# ADXL375_BOARD.net
KiCad netlist of a schematic drawn in EAGLE
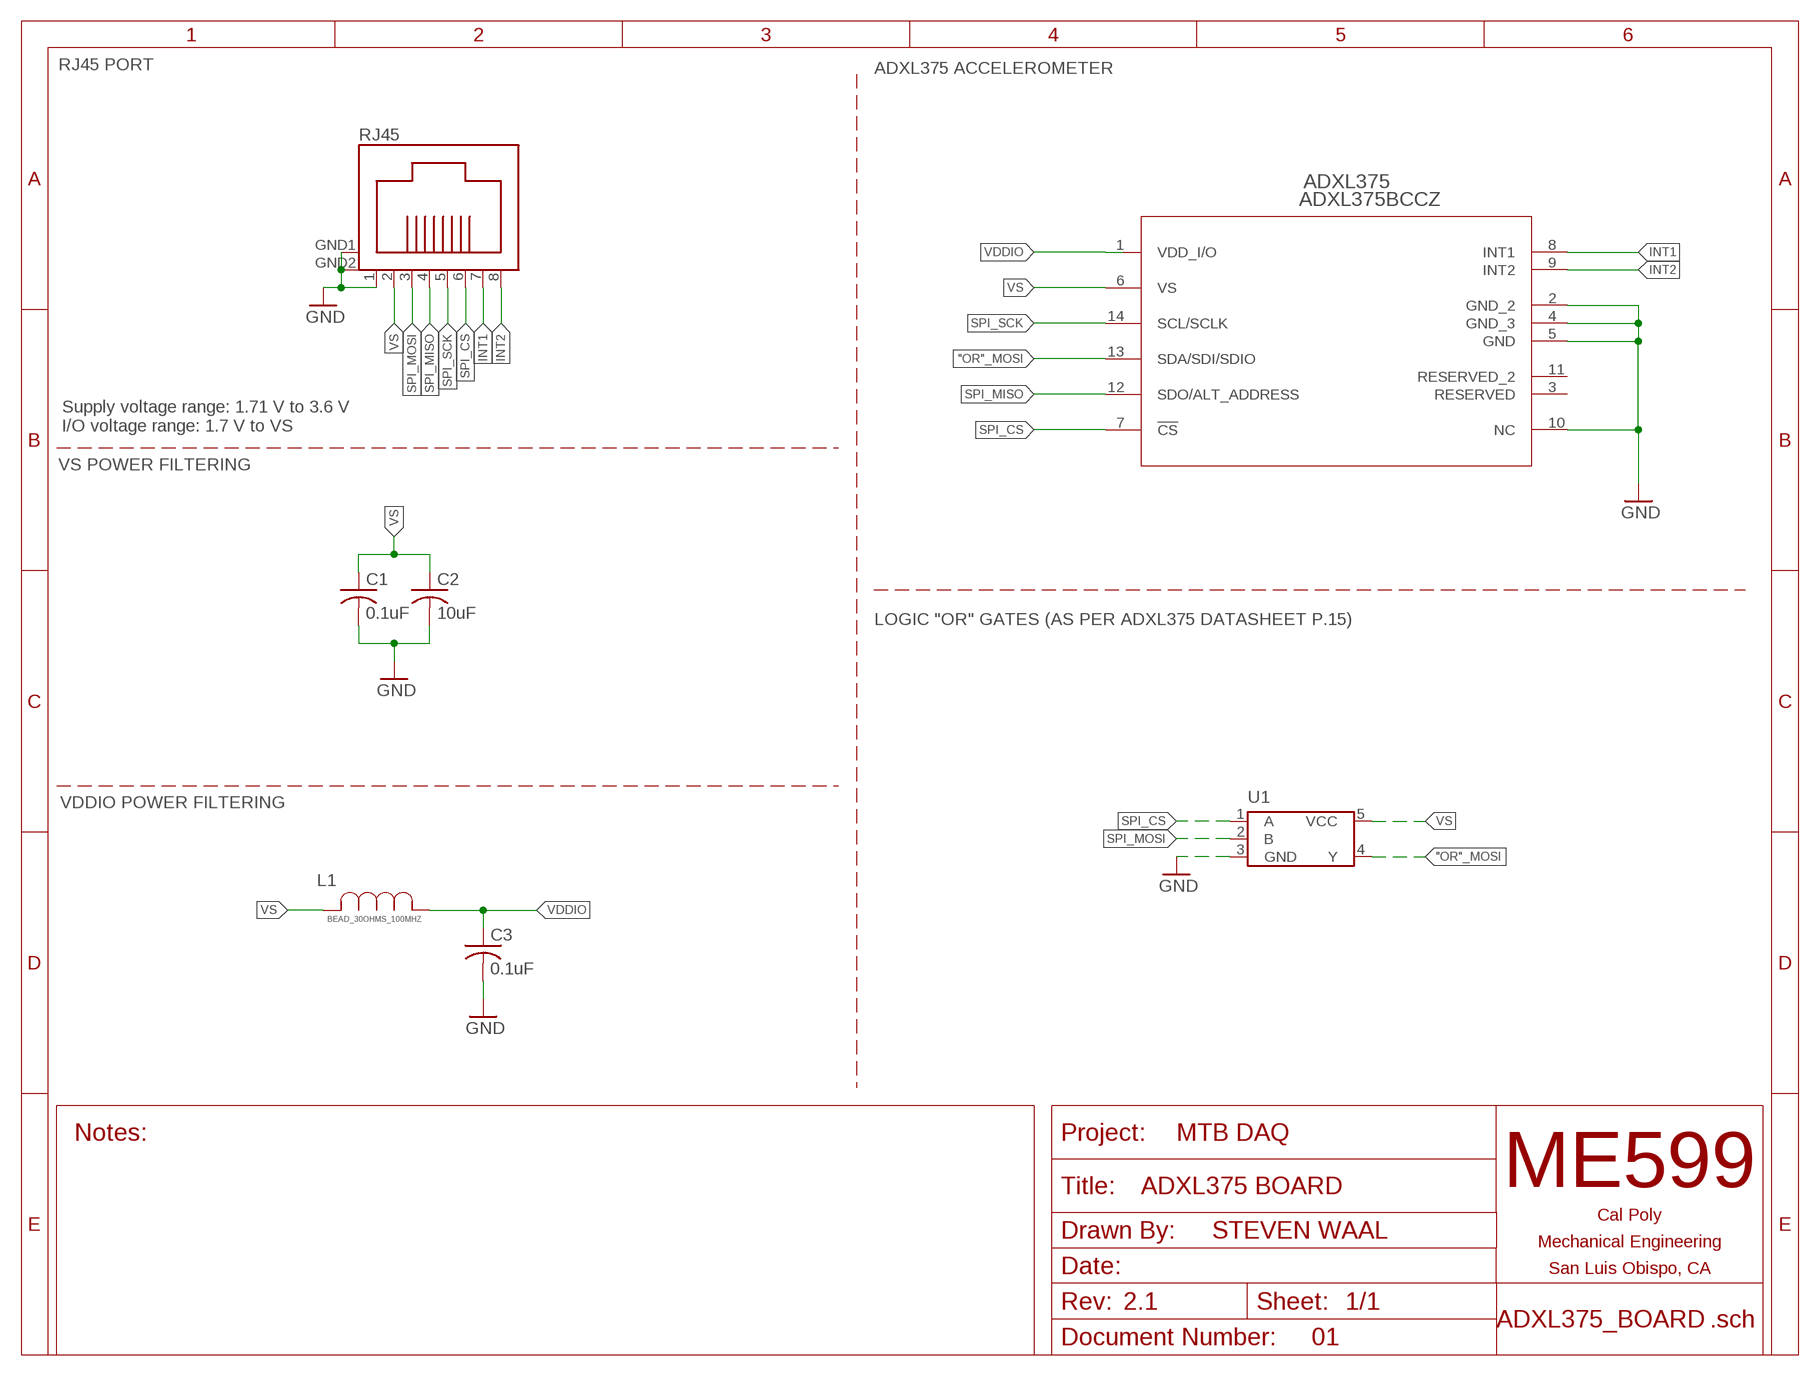
[diagram p0: schematic, sheet 1]

(export (version "E")
  (design (tool "Eeschema 10.0.6"))
  (components
    (comp (ref "ADXL375")
      (value "ADXL375BCCZ")
      (footprint "eagle-import:LGA_CC-14-1")
      (libsource (lib "eagle-import") (part "ADXL375BCCZ"))
    )
    (comp (ref "C1")
      (value "0.1uF")
      (footprint "eagle-import:C0805")
      (libsource (lib "eagle-import") (part "C-USC0805"))
    )
    (comp (ref "C2")
      (value "10uF")
      (footprint "eagle-import:C0805")
      (libsource (lib "eagle-import") (part "C-USC0805"))
    )
    (comp (ref "C3")
      (value "0.1uF")
      (footprint "eagle-import:C0805")
      (libsource (lib "eagle-import") (part "C-USC0805"))
    )
    (comp (ref "L1")
      (value "BEAD_30OHMS_100MHZ")
      (footprint "eagle-import:IND_BOURNS_MH2029")
      (fields (field (name "MANUFACTURER_PART_NUMBER") "MH2029300Y"))
      (libsource (lib "eagle-import") (part "BEAD_30OHMS_100MHZ"))
    )
    (comp (ref "RJ45")
      (value "RJ45_SURFACE_MOUNT")
      (footprint "eagle-import:RJ45_SURFACE_MOUNT")
      (libsource (lib "eagle-import") (part "RJ45_SURFACE_MOUNT"))
    )
    (comp (ref "U1")
      (value "SN74LVC1G32DCKR")
      (footprint "eagle-import:DCK5")
      (fields (field (name "MANUFACTURER") "Texas Instruments"))
      (libsource (lib "eagle-import") (part "SN74LVC1G32DCKR"))
    )
  )
  (nets
    (net (code "1") (name "\"OR\"_MOSI") (class "Default")
      (node (ref "ADXL375") (pin "13") (pinfunction "SDA/SDI/SDIO_13") (pintype "passive"))
      (node (ref "U1") (pin "4") (pinfunction "Y_4") (pintype "output"))
    )
    (net (code "2") (name "GND") (class "Default")
      (node (ref "ADXL375") (pin "10") (pinfunction "NC_10") (pintype "passive"))
      (node (ref "ADXL375") (pin "2") (pinfunction "GND_2_2") (pintype "passive"))
      (node (ref "ADXL375") (pin "4") (pinfunction "GND_3_4") (pintype "passive"))
      (node (ref "ADXL375") (pin "5") (pinfunction "GND_5") (pintype "passive"))
      (node (ref "C1") (pin "2") (pinfunction "2_2") (pintype "passive"))
      (node (ref "C2") (pin "2") (pinfunction "2_2") (pintype "passive"))
      (node (ref "C3") (pin "2") (pinfunction "2_2") (pintype "passive"))
      (node (ref "RJ45") (pin "1") (pinfunction "1_1") (pintype "passive"))
      (node (ref "RJ45") (pin "GND1") (pinfunction "GND1_GND1") (pintype "power_in"))
      (node (ref "RJ45") (pin "GND2") (pinfunction "GND2_GND2") (pintype "power_in"))
      (node (ref "U1") (pin "3") (pinfunction "GND_3") (pintype "power_in"))
    )
    (net (code "3") (name "INT1") (class "Default")
      (node (ref "ADXL375") (pin "8") (pinfunction "INT1_8") (pintype "passive"))
      (node (ref "RJ45") (pin "7") (pinfunction "7_7") (pintype "passive"))
    )
    (net (code "4") (name "INT2") (class "Default")
      (node (ref "ADXL375") (pin "9") (pinfunction "INT2_9") (pintype "passive"))
      (node (ref "RJ45") (pin "8") (pinfunction "8_8") (pintype "passive"))
    )
    (net (code "5") (name "SPI_CS") (class "Default")
      (node (ref "ADXL375") (pin "7") (pinfunction "~{CS}_7") (pintype "passive"))
      (node (ref "RJ45") (pin "6") (pinfunction "6_6") (pintype "passive"))
      (node (ref "U1") (pin "1") (pinfunction "A_1") (pintype "input"))
    )
    (net (code "6") (name "SPI_MISO") (class "Default")
      (node (ref "ADXL375") (pin "12") (pinfunction "SDO/ALT_ADDRESS_12") (pintype "passive"))
      (node (ref "RJ45") (pin "4") (pinfunction "4_4") (pintype "passive"))
    )
    (net (code "7") (name "SPI_MOSI") (class "Default")
      (node (ref "RJ45") (pin "3") (pinfunction "3_3") (pintype "passive"))
      (node (ref "U1") (pin "2") (pinfunction "B_2") (pintype "input"))
    )
    (net (code "8") (name "SPI_SCK") (class "Default")
      (node (ref "ADXL375") (pin "14") (pinfunction "SCL/SCLK_14") (pintype "passive"))
      (node (ref "RJ45") (pin "5") (pinfunction "5_5") (pintype "passive"))
    )
    (net (code "9") (name "VDDIO") (class "Default")
      (node (ref "ADXL375") (pin "1") (pinfunction "VDD_I/O_1") (pintype "passive"))
      (node (ref "C3") (pin "1") (pinfunction "1_1") (pintype "passive"))
      (node (ref "L1") (pin "1") (pinfunction "1_1") (pintype "passive"))
    )
    (net (code "10") (name "VS") (class "Default")
      (node (ref "ADXL375") (pin "6") (pinfunction "VS_6") (pintype "passive"))
      (node (ref "C1") (pin "1") (pinfunction "1_1") (pintype "passive"))
      (node (ref "C2") (pin "1") (pinfunction "1_1") (pintype "passive"))
      (node (ref "L1") (pin "2") (pinfunction "2_2") (pintype "passive"))
      (node (ref "RJ45") (pin "2") (pinfunction "2_2") (pintype "passive"))
      (node (ref "U1") (pin "5") (pinfunction "VCC_5") (pintype "power_in"))
    )
    (net (code "11") (name "unconnected-(ADXL375-RESERVED-Pad3)") (class "Default")
      (node (ref "ADXL375") (pin "3") (pinfunction "RESERVED_3") (pintype "passive"))
    )
    (net (code "12") (name "unconnected-(ADXL375-RESERVED_2-Pad11)") (class "Default")
      (node (ref "ADXL375") (pin "11") (pinfunction "RESERVED_2_11") (pintype "passive"))
    )
  )
)
